# Voltage_Regulation_old.net
KiCad netlist of a schematic drawn in Altium Designer
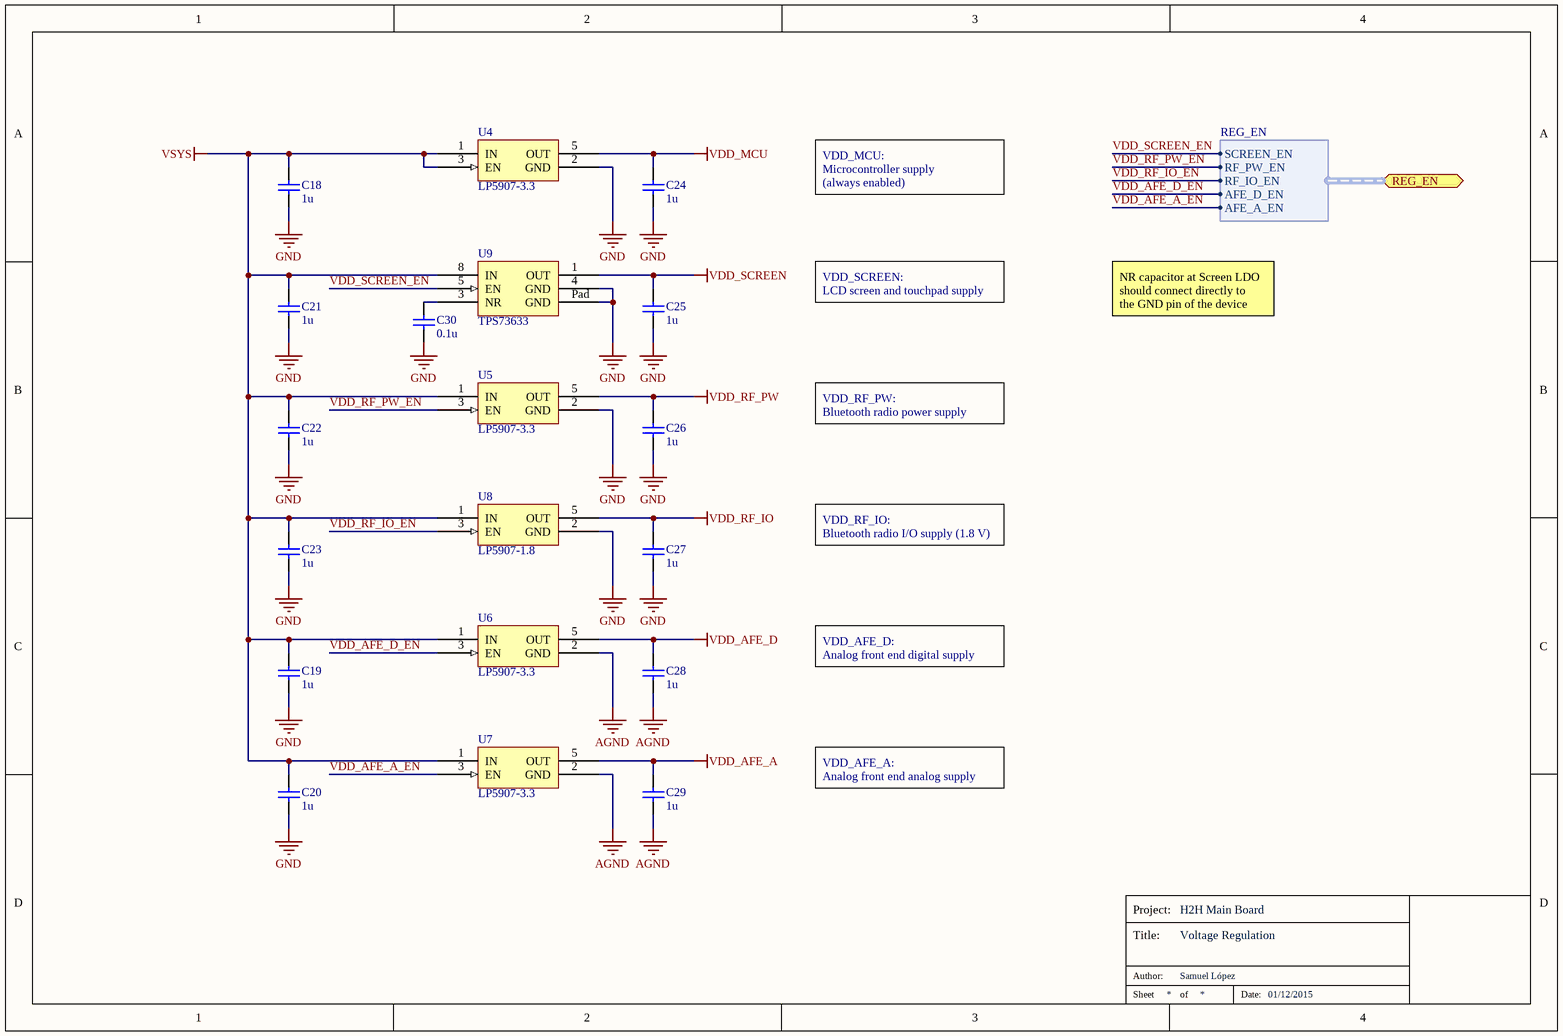
[diagram p0: Voltage Regulation_old.SchDoc]

(export (version "E")
  (design (tool "Eeschema 10.0.6"))
  (components
    (comp (ref "C18")
      (value "1u")
      (footprint "C0603")
      (description "Capacitor")
      (libsource (lib "Common Devices") (part "Capacitor"))
    )
    (comp (ref "C19")
      (value "1u")
      (footprint "C0603")
      (description "Capacitor")
      (libsource (lib "Common Devices") (part "Capacitor"))
    )
    (comp (ref "C20")
      (value "1u")
      (footprint "C0603")
      (description "Capacitor")
      (libsource (lib "Common Devices") (part "Capacitor"))
    )
    (comp (ref "C21")
      (value "1u")
      (footprint "C0603")
      (description "Capacitor")
      (libsource (lib "Common Devices") (part "Capacitor"))
    )
    (comp (ref "C22")
      (value "1u")
      (footprint "C0603")
      (description "Capacitor")
      (libsource (lib "Common Devices") (part "Capacitor"))
    )
    (comp (ref "C23")
      (value "1u")
      (footprint "C0603")
      (description "Capacitor")
      (libsource (lib "Common Devices") (part "Capacitor"))
    )
    (comp (ref "C24")
      (value "1u")
      (footprint "C0603")
      (description "Capacitor")
      (libsource (lib "Common Devices") (part "Capacitor"))
    )
    (comp (ref "C25")
      (value "1u")
      (footprint "C0603")
      (description "Capacitor")
      (libsource (lib "Common Devices") (part "Capacitor"))
    )
    (comp (ref "C26")
      (value "1u")
      (footprint "C0603")
      (description "Capacitor")
      (libsource (lib "Common Devices") (part "Capacitor"))
    )
    (comp (ref "C27")
      (value "1u")
      (footprint "C0603")
      (description "Capacitor")
      (libsource (lib "Common Devices") (part "Capacitor"))
    )
    (comp (ref "C28")
      (value "1u")
      (footprint "C0603")
      (description "Capacitor")
      (libsource (lib "Common Devices") (part "Capacitor"))
    )
    (comp (ref "C29")
      (value "1u")
      (footprint "C0603")
      (description "Capacitor")
      (libsource (lib "Common Devices") (part "Capacitor"))
    )
    (comp (ref "C30")
      (value "0.1u")
      (footprint "C0603")
      (description "Capacitor")
      (libsource (lib "Common Devices") (part "Capacitor"))
    )
    (comp (ref "U4")
      (value "LP5907-3.3")
      (footprint "SOT23")
      (description "Voltage Regulator - Linear")
      (libsource (lib "Main Board") (part "LP5907-3.3"))
    )
    (comp (ref "U5")
      (value "LP5907-3.3")
      (footprint "SOT23")
      (description "Voltage Regulator - Linear")
      (libsource (lib "Main Board") (part "LP5907-3.3"))
    )
    (comp (ref "U6")
      (value "LP5907-3.3")
      (footprint "SOT23")
      (description "Voltage Regulator - Linear")
      (libsource (lib "Main Board") (part "LP5907-3.3"))
    )
    (comp (ref "U7")
      (value "LP5907-3.3")
      (footprint "SOT23")
      (description "Voltage Regulator - Linear")
      (libsource (lib "Main Board") (part "LP5907-3.3"))
    )
    (comp (ref "U8")
      (value "LP5907-1.8")
      (footprint "SOT23")
      (description "Voltage Regulator - Linear")
      (libsource (lib "Main Board") (part "LP5907-1.8"))
    )
    (comp (ref "U9")
      (value "TPS73633")
      (footprint "PSON65P300X100_HS-9N")
      (description "Voltage Regulator - Linear")
      (libsource (lib "Main Board") (part "TPS73633"))
    )
  )
  (nets
    (net (code "2") (name "/VDD_AFE_A_EN") (class "Default")
      (node (ref "U7") (pin "3") (pinfunction "EN_3") (pintype "input"))
    )
    (net (code "3") (name "/VDD_AFE_D_EN") (class "Default")
      (node (ref "U6") (pin "3") (pinfunction "EN_3") (pintype "input"))
    )
    (net (code "4") (name "/VDD_RF_IO_EN") (class "Default")
      (node (ref "U8") (pin "3") (pinfunction "EN_3") (pintype "input"))
    )
    (net (code "5") (name "/VDD_RF_PW_EN") (class "Default")
      (node (ref "U5") (pin "3") (pinfunction "EN_3") (pintype "input"))
    )
    (net (code "6") (name "/VDD_SCREEN_EN") (class "Default")
      (node (ref "U9") (pin "5") (pinfunction "EN_5") (pintype "input"))
    )
    (net (code "8") (name "AGND") (class "Default")
      (node (ref "C28") (pin "1") (pinfunction "1_1") (pintype "passive"))
      (node (ref "C29") (pin "1") (pinfunction "1_1") (pintype "passive"))
      (node (ref "U6") (pin "2") (pinfunction "GND_2") (pintype "power_in"))
      (node (ref "U7") (pin "2") (pinfunction "GND_2") (pintype "power_in"))
    )
    (net (code "9") (name "GND") (class "Default")
      (node (ref "C18") (pin "1") (pinfunction "1_1") (pintype "passive"))
      (node (ref "C19") (pin "1") (pinfunction "1_1") (pintype "passive"))
      (node (ref "C20") (pin "1") (pinfunction "1_1") (pintype "passive"))
      (node (ref "C21") (pin "1") (pinfunction "1_1") (pintype "passive"))
      (node (ref "C22") (pin "1") (pinfunction "1_1") (pintype "passive"))
      (node (ref "C23") (pin "1") (pinfunction "1_1") (pintype "passive"))
      (node (ref "C24") (pin "1") (pinfunction "1_1") (pintype "passive"))
      (node (ref "C25") (pin "1") (pinfunction "1_1") (pintype "passive"))
      (node (ref "C26") (pin "1") (pinfunction "1_1") (pintype "passive"))
      (node (ref "C27") (pin "1") (pinfunction "1_1") (pintype "passive"))
      (node (ref "C30") (pin "1") (pinfunction "1_1") (pintype "passive"))
      (node (ref "U4") (pin "2") (pinfunction "GND_2") (pintype "power_in"))
      (node (ref "U5") (pin "2") (pinfunction "GND_2") (pintype "power_in"))
      (node (ref "U8") (pin "2") (pinfunction "GND_2") (pintype "power_in"))
      (node (ref "U9") (pin "4") (pinfunction "GND_4") (pintype "power_in"))
      (node (ref "U9") (pin "Pad") (pinfunction "GND_Pad") (pintype "power_in"))
    )
    (net (code "10") (name "Net-(U9-NR)") (class "Default")
      (node (ref "C30") (pin "2") (pinfunction "2_2") (pintype "passive"))
      (node (ref "U9") (pin "3") (pinfunction "NR_3") (pintype "passive"))
    )
    (net (code "11") (name "VDD_AFE_A") (class "Default")
      (node (ref "C29") (pin "2") (pinfunction "2_2") (pintype "passive"))
      (node (ref "U7") (pin "5") (pinfunction "OUT_5") (pintype "power_in"))
    )
    (net (code "12") (name "VDD_AFE_D") (class "Default")
      (node (ref "C28") (pin "2") (pinfunction "2_2") (pintype "passive"))
      (node (ref "U6") (pin "5") (pinfunction "OUT_5") (pintype "power_in"))
    )
    (net (code "13") (name "VDD_MCU") (class "Default")
      (node (ref "C24") (pin "2") (pinfunction "2_2") (pintype "passive"))
      (node (ref "U4") (pin "5") (pinfunction "OUT_5") (pintype "power_in"))
    )
    (net (code "14") (name "VDD_RF_IO") (class "Default")
      (node (ref "C27") (pin "2") (pinfunction "2_2") (pintype "passive"))
      (node (ref "U8") (pin "5") (pinfunction "OUT_5") (pintype "power_in"))
    )
    (net (code "15") (name "VDD_RF_PW") (class "Default")
      (node (ref "C26") (pin "2") (pinfunction "2_2") (pintype "passive"))
      (node (ref "U5") (pin "5") (pinfunction "OUT_5") (pintype "power_in"))
    )
    (net (code "16") (name "VDD_SCREEN") (class "Default")
      (node (ref "C25") (pin "2") (pinfunction "2_2") (pintype "passive"))
      (node (ref "U9") (pin "1") (pinfunction "OUT_1") (pintype "power_in"))
    )
    (net (code "17") (name "VSYS") (class "Default")
      (node (ref "C18") (pin "2") (pinfunction "2_2") (pintype "passive"))
      (node (ref "C19") (pin "2") (pinfunction "2_2") (pintype "passive"))
      (node (ref "C20") (pin "2") (pinfunction "2_2") (pintype "passive"))
      (node (ref "C21") (pin "2") (pinfunction "2_2") (pintype "passive"))
      (node (ref "C22") (pin "2") (pinfunction "2_2") (pintype "passive"))
      (node (ref "C23") (pin "2") (pinfunction "2_2") (pintype "passive"))
      (node (ref "U4") (pin "1") (pinfunction "IN_1") (pintype "power_in"))
      (node (ref "U4") (pin "3") (pinfunction "EN_3") (pintype "input"))
      (node (ref "U5") (pin "1") (pinfunction "IN_1") (pintype "power_in"))
      (node (ref "U6") (pin "1") (pinfunction "IN_1") (pintype "power_in"))
      (node (ref "U7") (pin "1") (pinfunction "IN_1") (pintype "power_in"))
      (node (ref "U8") (pin "1") (pinfunction "IN_1") (pintype "power_in"))
      (node (ref "U9") (pin "8") (pinfunction "IN_8") (pintype "power_in"))
    )
  )
)
